# VESC6.net
KiCad netlist of a schematic drawn in Altium Designer
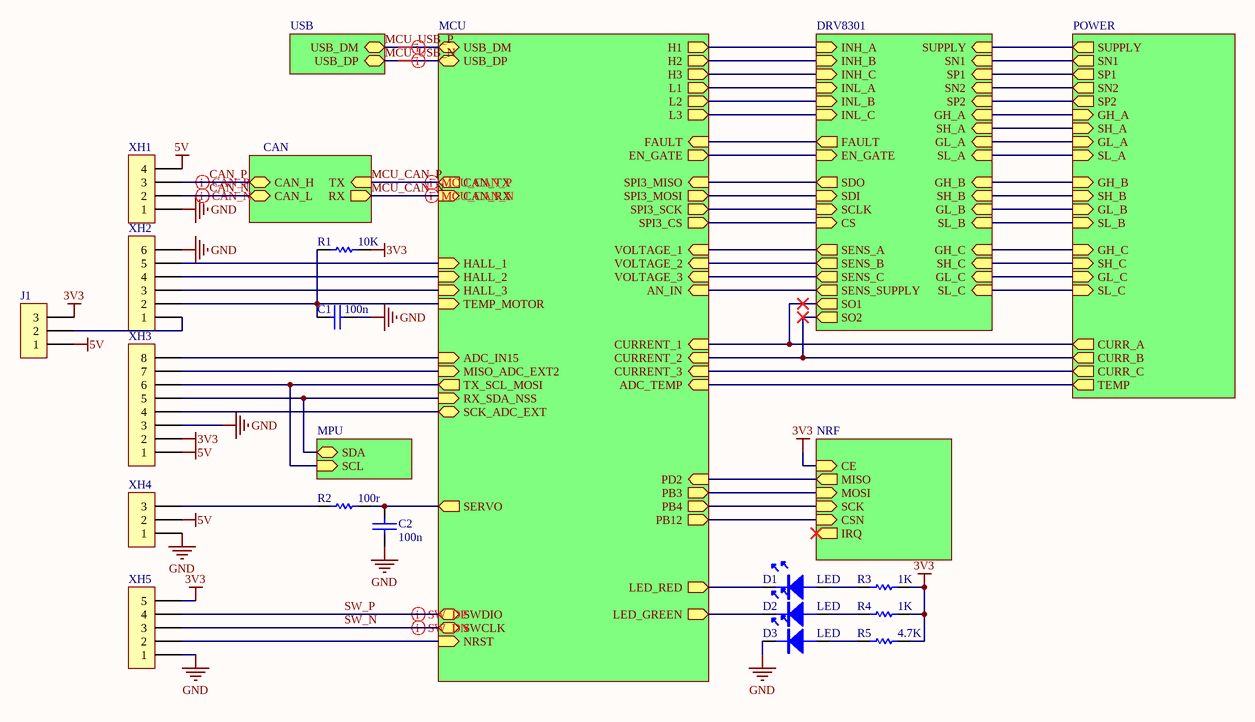
[diagram p0: VESC6.SchDoc]

(export (version "E")
  (design (tool "Eeschema 10.0.6"))
  (components
    (comp (ref "C1")
      (value "100n")
      (footprint "0603C")
      (description "无极性电容")
      (libsource (lib "电容") (part "CAP"))
    )
    (comp (ref "C2")
      (value "100n")
      (footprint "0603C")
      (description "无极性电容")
      (libsource (lib "电容") (part "CAP"))
    )
    (comp (ref "D1") (value "LED") (footprint "LED-0603Y") (libsource (lib "LED") (part "LED")))
    (comp (ref "D2") (value "LED") (footprint "LED-0603Y") (libsource (lib "LED") (part "LED")))
    (comp (ref "D3") (value "LED") (footprint "LED-0603Y") (libsource (lib "LED") (part "LED")))
    (comp (ref "J1")
      (value "Pin HDR1X3")
      (footprint "Pin HDR1X3/2.54mm-S")
      (libsource (lib "排针") (part "Pin HDR1X3"))
    )
    (comp (ref "R1") (value "10K") (footprint "0603R") (libsource (lib "电阻") (part "RES")))
    (comp (ref "R2") (value "100r") (footprint "0603R") (libsource (lib "电阻") (part "RES")))
    (comp (ref "R3") (value "1K") (footprint "0603R") (libsource (lib "电阻") (part "RES")))
    (comp (ref "R4") (value "1K") (footprint "0603R") (libsource (lib "电阻") (part "RES")))
    (comp (ref "R5") (value "4.7K") (footprint "0603R") (libsource (lib "电阻") (part "RES")))
    (comp (ref "XH1") (value "XH4") (footprint "XH4/2.54mm/90") (libsource (lib "XH，VH") (part "XH4")))
    (comp (ref "XH2") (value "XH6") (footprint "XH6/2.54mm/90") (libsource (lib "XH，VH") (part "XH6")))
    (comp (ref "XH3") (value "XH8") (footprint "XH8/2.54mm/90") (libsource (lib "XH，VH") (part "XH8")))
    (comp (ref "XH4") (value "XH3") (footprint "XH3/2.54mm/90") (libsource (lib "XH，VH") (part "XH3")))
    (comp (ref "XH5") (value "XH5") (footprint "XH5/2.54mm/90") (libsource (lib "XH，VH") (part "XH5")))
  )
  (nets
    (net (code "1") (name "/ADC_IN15") (class "Default")
      (node (ref "XH3") (pin "8") (pinfunction "8_8") (pintype "passive"))
    )
    (net (code "2") (name "/CAN_N") (class "Default")
      (node (ref "XH1") (pin "2") (pinfunction "2_2") (pintype "passive"))
    )
    (net (code "3") (name "/CAN_P") (class "Default")
      (node (ref "XH1") (pin "3") (pinfunction "3_3") (pintype "passive"))
    )
    (net (code "18") (name "/HALL_1") (class "Default")
      (node (ref "XH2") (pin "5") (pinfunction "5_5") (pintype "passive"))
    )
    (net (code "19") (name "/HALL_2") (class "Default")
      (node (ref "XH2") (pin "4") (pinfunction "4_4") (pintype "passive"))
    )
    (net (code "20") (name "/HALL_3") (class "Default")
      (node (ref "XH2") (pin "3") (pinfunction "3_3") (pintype "passive"))
    )
    (net (code "25") (name "/LED_GREEN") (class "Default")
      (node (ref "D2") (pin "K") (pinfunction "K_K") (pintype "passive"))
    )
    (net (code "26") (name "/LED_RED") (class "Default")
      (node (ref "D1") (pin "K") (pinfunction "K_K") (pintype "passive"))
    )
    (net (code "32") (name "/MISO_ADC_EXT2") (class "Default")
      (node (ref "XH3") (pin "7") (pinfunction "7_7") (pintype "passive"))
    )
    (net (code "33") (name "/NRST") (class "Default")
      (node (ref "XH5") (pin "2") (pinfunction "2_2") (pintype "passive"))
    )
    (net (code "37") (name "/RX_SDA_NSS") (class "Default")
      (node (ref "XH3") (pin "5") (pinfunction "5_5") (pintype "passive"))
    )
    (net (code "38") (name "/SCK_ADC_EXT") (class "Default")
      (node (ref "XH3") (pin "4") (pinfunction "4_4") (pintype "passive"))
    )
    (net (code "44") (name "/SERVO") (class "Default")
      (node (ref "C2") (pin "2") (pinfunction "2_2") (pintype "passive"))
      (node (ref "R2") (pin "2") (pinfunction "2_2") (pintype "passive"))
    )
    (net (code "59") (name "/SW_N") (class "Default")
      (node (ref "XH5") (pin "3") (pinfunction "3_3") (pintype "passive"))
    )
    (net (code "60") (name "/SW_P") (class "Default")
      (node (ref "XH5") (pin "4") (pinfunction "4_4") (pintype "passive"))
    )
    (net (code "62") (name "/TEMP_MOTOR") (class "Default")
      (node (ref "C1") (pin "1") (pinfunction "1_1") (pintype "passive"))
      (node (ref "R1") (pin "1") (pinfunction "1_1") (pintype "passive"))
      (node (ref "XH2") (pin "2") (pinfunction "2_2") (pintype "passive"))
    )
    (net (code "63") (name "/TX_SCL_MOSI") (class "Default")
      (node (ref "XH3") (pin "6") (pinfunction "6_6") (pintype "passive"))
    )
    (net (code "64") (name "3V3") (class "Default")
      (node (ref "J1") (pin "3") (pinfunction "3_3") (pintype "passive"))
      (node (ref "R1") (pin "2") (pinfunction "2_2") (pintype "passive"))
      (node (ref "R3") (pin "2") (pinfunction "2_2") (pintype "passive"))
      (node (ref "R4") (pin "2") (pinfunction "2_2") (pintype "passive"))
      (node (ref "R5") (pin "2") (pinfunction "2_2") (pintype "passive"))
      (node (ref "XH3") (pin "2") (pinfunction "2_2") (pintype "passive"))
      (node (ref "XH5") (pin "5") (pinfunction "5_5") (pintype "passive"))
    )
    (net (code "65") (name "5V") (class "Default")
      (node (ref "J1") (pin "1") (pinfunction "1_1") (pintype "passive"))
      (node (ref "XH1") (pin "4") (pinfunction "4_4") (pintype "passive"))
      (node (ref "XH3") (pin "1") (pinfunction "1_1") (pintype "passive"))
      (node (ref "XH4") (pin "2") (pinfunction "2_2") (pintype "passive"))
    )
    (net (code "66") (name "GND") (class "Default")
      (node (ref "C1") (pin "2") (pinfunction "2_2") (pintype "passive"))
      (node (ref "C2") (pin "1") (pinfunction "1_1") (pintype "passive"))
      (node (ref "D3") (pin "K") (pinfunction "K_K") (pintype "passive"))
      (node (ref "XH1") (pin "1") (pinfunction "1_1") (pintype "passive"))
      (node (ref "XH2") (pin "6") (pinfunction "6_6") (pintype "passive"))
      (node (ref "XH3") (pin "3") (pinfunction "3_3") (pintype "passive"))
      (node (ref "XH4") (pin "1") (pinfunction "1_1") (pintype "passive"))
      (node (ref "XH5") (pin "1") (pinfunction "1_1") (pintype "passive"))
    )
    (net (code "67") (name "Net-(D1-PadA)") (class "Default")
      (node (ref "D1") (pin "A") (pinfunction "A_A") (pintype "passive"))
      (node (ref "R3") (pin "1") (pinfunction "1_1") (pintype "passive"))
    )
    (net (code "68") (name "Net-(D2-PadA)") (class "Default")
      (node (ref "D2") (pin "A") (pinfunction "A_A") (pintype "passive"))
      (node (ref "R4") (pin "1") (pinfunction "1_1") (pintype "passive"))
    )
    (net (code "69") (name "Net-(D3-PadA)") (class "Default")
      (node (ref "D3") (pin "A") (pinfunction "A_A") (pintype "passive"))
      (node (ref "R5") (pin "1") (pinfunction "1_1") (pintype "passive"))
    )
    (net (code "70") (name "Net-(J1-Pad2)") (class "Default")
      (node (ref "J1") (pin "2") (pinfunction "2_2") (pintype "passive"))
      (node (ref "XH2") (pin "1") (pinfunction "1_1") (pintype "passive"))
    )
    (net (code "71") (name "Net-(R2-Pad1)") (class "Default")
      (node (ref "R2") (pin "1") (pinfunction "1_1") (pintype "passive"))
      (node (ref "XH4") (pin "3") (pinfunction "3_3") (pintype "passive"))
    )
  )
)
